# 411618_029_3_4.net
KiCad netlist of a schematic drawn in Altium Designer
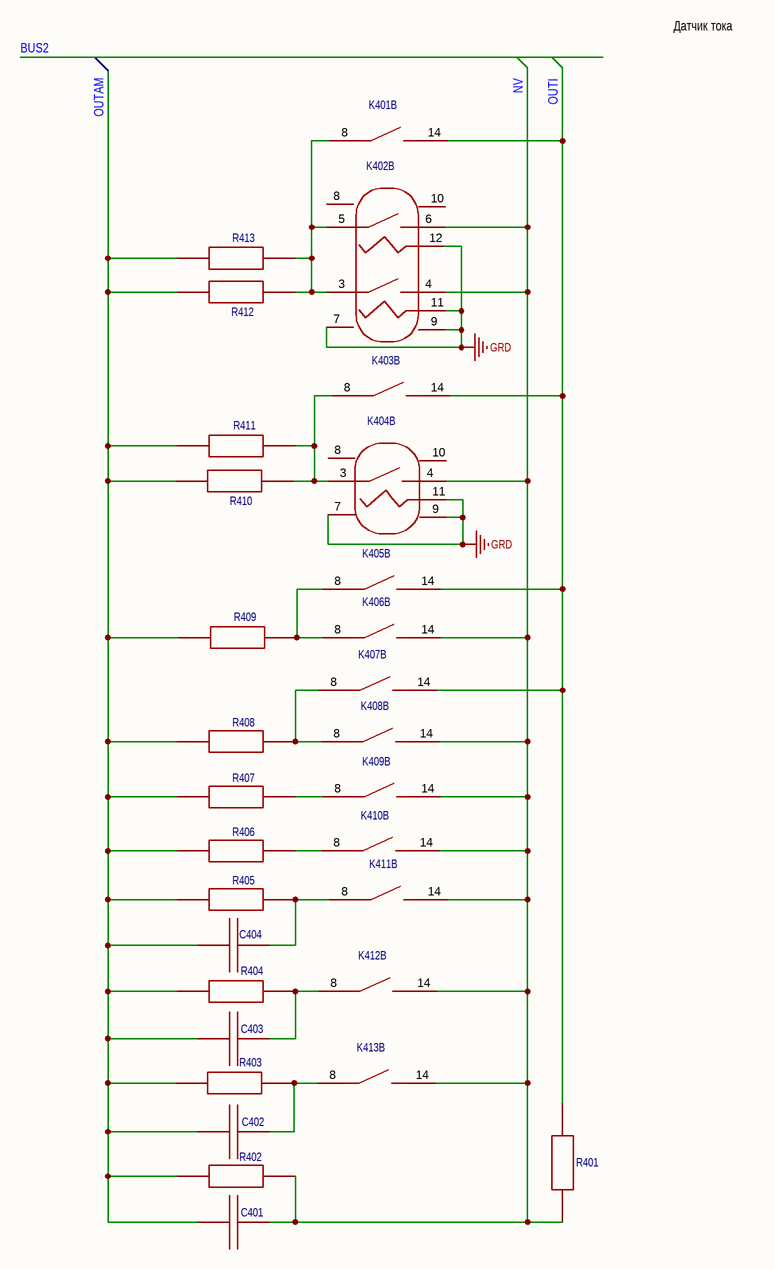
[diagram p0: УШЯИ.411618.029Э Э3 Лист 4.schdoc]

(export (version "E")
  (design (tool "Eeschema 10.0.6"))
  (components
    (comp (ref "C401")
      (value "Конденсатор К10-17Б М47 33пФ NP0 5% [DIP]")
      (fields (field (name "MANUFACTURER PART") "К10-17Б М47") (field (name "CONTRIBUTOR") "jordanjin"))
      (libsource (lib "altium-import") (part "root_2_Конденсатор К10-17Б М47 33пФ NP0 5% [DIP]_"))
    )
    (comp (ref "C402")
      (value "Конденсатор К10-17Б М47 33пФ NP0 5% [DIP]")
      (fields (field (name "MANUFACTURER PART") "К10-17Б М47") (field (name "CONTRIBUTOR") "jordanjin"))
      (libsource (lib "altium-import") (part "root_2_Конденсатор К10-17Б М47 33пФ NP0 5% [DIP]_"))
    )
    (comp (ref "C403")
      (value "Конденсатор К10-17Б М47 33пФ NP0 5% [DIP]")
      (fields (field (name "MANUFACTURER PART") "К10-17Б М47") (field (name "CONTRIBUTOR") "jordanjin"))
      (libsource (lib "altium-import") (part "root_2_Конденсатор К10-17Б М47 33пФ NP0 5% [DIP]_"))
    )
    (comp (ref "C404")
      (value "Конденсатор К10-17Б М47 33пФ NP0 5% [DIP]")
      (fields (field (name "MANUFACTURER PART") "К10-17Б М47") (field (name "CONTRIBUTOR") "jordanjin"))
      (libsource (lib "altium-import") (part "root_2_Конденсатор К10-17Б М47 33пФ NP0 5% [DIP]_"))
    )
    (comp (ref "K401")
      (value "Реле герконовое DIP05-1A72-13L  [PCB]")
      (footprint "RELAY-TH_STANDEXMEDER_DIP05-1A72-13L")
      (fields
        (field (name "MANUFACTURER") "STANDEXMEDER")
        (field (name "MANUFACTURER PART") "DIP05-1A72-13L")
        (field (name "SUBPART_NO") "1")
        (field (name "CONTRIBUTOR") "jordanjin")
      )
      (libsource (lib "altium-import") (part "root_1_Реле герконовое DIP05-1A72-13L  [PCB]_"))
    )
    (comp (ref "K402")
      (value "Реле герконовое УШЯИ.685442.092 (2 реле)")
      (fields
        (field (name "MANUFACTURER") "ОАО\"МНИПИ\"")
        (field (name "MANUFACTURER PART") "УШЯИ.685442.092")
        (field (name "PART NUMBER") "1")
        (field (name "CONTRIBUTOR") "jordanjin")
      )
      (libsource (lib "altium-import") (part "root_1_Реле герконовое УШЯИ.685442.092 (2 реле)_"))
    )
    (comp (ref "K403")
      (value "Реле герконовое DIP05-1A72-13L  [PCB]")
      (footprint "RELAY-TH_STANDEXMEDER_DIP05-1A72-13L")
      (fields
        (field (name "MANUFACTURER") "STANDEXMEDER")
        (field (name "MANUFACTURER PART") "DIP05-1A72-13L")
        (field (name "SUBPART_NO") "1")
        (field (name "CONTRIBUTOR") "jordanjin")
      )
      (libsource (lib "altium-import") (part "root_1_Реле герконовое DIP05-1A72-13L  [PCB]_"))
    )
    (comp (ref "K404")
      (value "Реле герконовое УШЯИ.685442.092 (1 реле)")
      (fields
        (field (name "MANUFACTURER") "ОАО\"МНИПИ\"")
        (field (name "MANUFACTURER PART") "УШЯИ.685442.092")
        (field (name "SUBPART_NO") "1")
        (field (name "CONTRIBUTOR") "jordanjin")
      )
      (libsource (lib "altium-import") (part "root_1_Реле герконовое УШЯИ.685442.092 (1 реле)_"))
    )
    (comp (ref "K405")
      (value "Реле герконовое DIP05-1A72-13L  [PCB]")
      (footprint "RELAY-TH_STANDEXMEDER_DIP05-1A72-13L")
      (fields
        (field (name "MANUFACTURER") "STANDEXMEDER")
        (field (name "MANUFACTURER PART") "DIP05-1A72-13L")
        (field (name "SUBPART_NO") "1")
        (field (name "CONTRIBUTOR") "jordanjin")
      )
      (libsource (lib "altium-import") (part "root_1_Реле герконовое DIP05-1A72-13L  [PCB]_"))
    )
    (comp (ref "K406")
      (value "Реле герконовое DIP05-1A72-13L  [PCB]")
      (footprint "RELAY-TH_STANDEXMEDER_DIP05-1A72-13L")
      (fields
        (field (name "MANUFACTURER") "STANDEXMEDER")
        (field (name "MANUFACTURER PART") "DIP05-1A72-13L")
        (field (name "SUBPART_NO") "1")
        (field (name "CONTRIBUTOR") "jordanjin")
      )
      (libsource (lib "altium-import") (part "root_1_Реле герконовое DIP05-1A72-13L  [PCB]_"))
    )
    (comp (ref "K407")
      (value "Реле герконовое DIP05-1A72-13L  [PCB]")
      (footprint "RELAY-TH_STANDEXMEDER_DIP05-1A72-13L")
      (fields
        (field (name "MANUFACTURER") "STANDEXMEDER")
        (field (name "MANUFACTURER PART") "DIP05-1A72-13L")
        (field (name "SUBPART_NO") "1")
        (field (name "CONTRIBUTOR") "jordanjin")
      )
      (libsource (lib "altium-import") (part "root_1_Реле герконовое DIP05-1A72-13L  [PCB]_"))
    )
    (comp (ref "K408")
      (value "Реле герконовое DIP05-1A72-13L  [PCB]")
      (footprint "RELAY-TH_STANDEXMEDER_DIP05-1A72-13L")
      (fields
        (field (name "MANUFACTURER") "STANDEXMEDER")
        (field (name "MANUFACTURER PART") "DIP05-1A72-13L")
        (field (name "SUBPART_NO") "1")
        (field (name "CONTRIBUTOR") "jordanjin")
      )
      (libsource (lib "altium-import") (part "root_1_Реле герконовое DIP05-1A72-13L  [PCB]_"))
    )
    (comp (ref "K409")
      (value "Реле герконовое DIP05-1A72-13L  [PCB]")
      (footprint "RELAY-TH_STANDEXMEDER_DIP05-1A72-13L")
      (fields
        (field (name "MANUFACTURER") "STANDEXMEDER")
        (field (name "MANUFACTURER PART") "DIP05-1A72-13L")
        (field (name "SUBPART_NO") "1")
        (field (name "CONTRIBUTOR") "jordanjin")
      )
      (libsource (lib "altium-import") (part "root_1_Реле герконовое DIP05-1A72-13L  [PCB]_"))
    )
    (comp (ref "K410")
      (value "Реле герконовое DIP05-1A72-13L  [PCB]")
      (footprint "RELAY-TH_STANDEXMEDER_DIP05-1A72-13L")
      (fields
        (field (name "MANUFACTURER") "STANDEXMEDER")
        (field (name "MANUFACTURER PART") "DIP05-1A72-13L")
        (field (name "SUBPART_NO") "1")
        (field (name "CONTRIBUTOR") "jordanjin")
      )
      (libsource (lib "altium-import") (part "root_1_Реле герконовое DIP05-1A72-13L  [PCB]_"))
    )
    (comp (ref "K411")
      (value "Реле герконовое DIP05-1A72-13L  [PCB]")
      (footprint "RELAY-TH_STANDEXMEDER_DIP05-1A72-13L")
      (fields
        (field (name "MANUFACTURER") "STANDEXMEDER")
        (field (name "MANUFACTURER PART") "DIP05-1A72-13L")
        (field (name "SUBPART_NO") "1")
        (field (name "CONTRIBUTOR") "jordanjin")
      )
      (libsource (lib "altium-import") (part "root_1_Реле герконовое DIP05-1A72-13L  [PCB]_"))
    )
    (comp (ref "K412")
      (value "Реле герконовое DIP05-1A72-13L  [PCB]")
      (footprint "RELAY-TH_STANDEXMEDER_DIP05-1A72-13L")
      (fields
        (field (name "MANUFACTURER") "STANDEXMEDER")
        (field (name "MANUFACTURER PART") "DIP05-1A72-13L")
        (field (name "SUBPART_NO") "1")
        (field (name "CONTRIBUTOR") "jordanjin")
      )
      (libsource (lib "altium-import") (part "root_1_Реле герконовое DIP05-1A72-13L  [PCB]_"))
    )
    (comp (ref "K413")
      (value "Реле герконовое DIP05-1A72-13L  [PCB]")
      (footprint "RELAY-TH_STANDEXMEDER_DIP05-1A72-13L")
      (fields
        (field (name "MANUFACTURER") "STANDEXMEDER")
        (field (name "MANUFACTURER PART") "DIP05-1A72-13L")
        (field (name "SUBPART_NO") "1")
        (field (name "CONTRIBUTOR") "jordanjin")
      )
      (libsource (lib "altium-import") (part "root_1_Реле герконовое DIP05-1A72-13L  [PCB]_"))
    )
    (comp (ref "R401")
      (value "Резистор C2-29В-0,25  24кОм ±0,5% [DIP]")
      (fields (field (name "MANUFACTURER PART") "C2-29В-0,25") (field (name "CONTRIBUTOR") "jordanjin"))
      (libsource (lib "altium-import") (part "root_1_Резистор C2-29В-0,25  24кОм ±0,5% [DIP]_"))
    )
    (comp (ref "R402")
      (value "Резистор SM204031006FE 100МОм ±1%[DIP]")
      (footprint "RES-TH_L27.4-W2.5-P22.86-D0.8")
      (fields
        (field (name "MANUFACTURER") "Ohmite")
        (field (name "MANUFACTURER PART") "SM204031006FE")
        (field (name "CONTRIBUTOR") "jordanjin")
      )
      (libsource (lib "altium-import") (part "root_2_Резистор SM204031006FE 100МОм ±1%[DIP]_"))
    )
    (comp (ref "R403")
      (value "Резистор RK1/4DCT52R1105F 11 МОм ±1% [DIP]")
      (fields
        (field (name "MANUFACTURER") "KOA Speer Electronics")
        (field (name "MANUFACTURER PART") "RK1/4DCT52R1105F")
        (field (name "CONTRIBUTOR") "jordanjin")
      )
      (libsource (lib "altium-import") (part "root_2_Резистор RK1/4DCT52R1105F 11 МОм ±1% [DIP]_"))
    )
    (comp (ref "R404")
      (value "Резистор C2-29В-0,25 1 МОм ±0,5% [DIP]")
      (fields (field (name "MANUFACTURER PART") "C2-29В-0,25") (field (name "CONTRIBUTOR") "jordanjin"))
      (libsource (lib "altium-import") (part "root_2_Резистор C2-29В-0,25 1 МОм ±0,5% [DIP]_"))
    )
    (comp (ref "R405")
      (value "Резистор C2-29В-0,25 100 кОм ±0,5% [DIP]")
      (fields (field (name "MANUFACTURER PART") "C2-29В-0,25") (field (name "CONTRIBUTOR") "jordanjin"))
      (libsource (lib "altium-import") (part "root_2_Резистор C2-29В-0,25 100 кОм ±0,5% [DIP]_"))
    )
    (comp (ref "R406")
      (value "Резистор C2-29B-1 10 кОм ±0,5% [DIP]")
      (fields (field (name "MANUFACTURER PART") "C2-29В-1") (field (name "CONTRIBUTOR") "jordanjin"))
      (libsource (lib "altium-import") (part "root_2_Резистор C2-29B-1 10 кОм ±0,5% [DIP]_"))
    )
    (comp (ref "R407")
      (value "Резистор C2-29B-1 1 кОм ±0,5% [DIP]")
      (fields (field (name "MANUFACTURER PART") "C2-29В-1") (field (name "CONTRIBUTOR") "jordanjin"))
      (libsource (lib "altium-import") (part "root_2_Резистор C2-29B-1 1 кОм ±0,5% [DIP]_"))
    )
    (comp (ref "R408")
      (value "Резистор C2-29B-1 100 Ом ±0,5% [DIP]")
      (fields (field (name "MANUFACTURER PART") "C2-29В-1") (field (name "CONTRIBUTOR") "jordanjin"))
      (libsource (lib "altium-import") (part "root_2_Резистор C2-29B-1 100 Ом ±0,5% [DIP]_"))
    )
    (comp (ref "R409")
      (value "Резистор C2-29B-2 10 Ом ±0,5% [DIP]")
      (fields (field (name "MANUFACTURER PART") "C2-29В-2") (field (name "CONTRIBUTOR") "jordanjin"))
      (libsource (lib "altium-import") (part "root_2_Резистор C2-29B-2 10 Ом ±0,5% [DIP]_"))
    )
    (comp (ref "R410")
      (value "Резистор MP930-2.00-1% [TO-220-2]")
      (footprint "TO-220-2_L10.4-W3.2-P5.08-L")
      (fields
        (field (name "MANUFACTURER") "Caddock")
        (field (name "MANUFACTURER PART") "MP930-2.00-1%")
        (field (name "CONTRIBUTOR") "jordanjin")
      )
      (libsource (lib "altium-import") (part "root_2_Резистор MP930-2.00-1% [TO-220-2]_"))
    )
    (comp (ref "R411")
      (value "Резистор MP930-2.00-1% [TO-220-2]")
      (footprint "TO-220-2_L10.4-W3.2-P5.08-L")
      (fields
        (field (name "MANUFACTURER") "Caddock")
        (field (name "MANUFACTURER PART") "MP930-2.00-1%")
        (field (name "CONTRIBUTOR") "jordanjin")
      )
      (libsource (lib "altium-import") (part "root_2_Резистор MP930-2.00-1% [TO-220-2]_"))
    )
    (comp (ref "R412")
      (value "Резистор MP930-0.20-1% [TO-220-2]")
      (footprint "TO-220-2_L10.4-W3.2-P5.08-L")
      (fields
        (field (name "MANUFACTURER") "Caddock")
        (field (name "MANUFACTURER PART") "MP930-2.00-1%")
        (field (name "CONTRIBUTOR") "jordanjin")
      )
      (libsource (lib "altium-import") (part "root_2_Резистор MP930-0.20-1% [TO-220-2]_"))
    )
    (comp (ref "R413")
      (value "Резистор MP930-0.20-1% [TO-220-2]")
      (footprint "TO-220-2_L10.4-W3.2-P5.08-L")
      (fields
        (field (name "MANUFACTURER") "Caddock")
        (field (name "MANUFACTURER PART") "MP930-2.00-1%")
        (field (name "CONTRIBUTOR") "jordanjin")
      )
      (libsource (lib "altium-import") (part "root_2_Резистор MP930-0.20-1% [TO-220-2]_"))
    )
  )
  (nets
    (net (code "2") (name "/NV") (class "Default")
      (node (ref "C401") (pin "1") (pinfunction "1_1") (pintype "passive"))
      (node (ref "K402") (pin "4") (pinfunction "4_4") (pintype "passive"))
      (node (ref "K402") (pin "6") (pinfunction "6_6") (pintype "passive"))
      (node (ref "K404") (pin "4") (pinfunction "4_4") (pintype "passive"))
      (node (ref "K406") (pin "14") (pinfunction "14_14") (pintype "passive"))
      (node (ref "K408") (pin "14") (pinfunction "14_14") (pintype "passive"))
      (node (ref "K409") (pin "14") (pinfunction "14_14") (pintype "passive"))
      (node (ref "K410") (pin "14") (pinfunction "14_14") (pintype "passive"))
      (node (ref "K411") (pin "14") (pinfunction "14_14") (pintype "passive"))
      (node (ref "K412") (pin "14") (pinfunction "14_14") (pintype "passive"))
      (node (ref "K413") (pin "14") (pinfunction "14_14") (pintype "passive"))
      (node (ref "R401") (pin "1") (pinfunction "1_1") (pintype "passive"))
      (node (ref "R402") (pin "1") (pinfunction "1_1") (pintype "passive"))
    )
    (net (code "3") (name "/OUTAM") (class "Default")
      (node (ref "C401") (pin "2") (pinfunction "2_2") (pintype "passive"))
      (node (ref "C402") (pin "2") (pinfunction "2_2") (pintype "passive"))
      (node (ref "C403") (pin "2") (pinfunction "2_2") (pintype "passive"))
      (node (ref "C404") (pin "2") (pinfunction "2_2") (pintype "passive"))
      (node (ref "R402") (pin "2") (pinfunction "2_2") (pintype "passive"))
      (node (ref "R403") (pin "2") (pinfunction "2_2") (pintype "passive"))
      (node (ref "R404") (pin "2") (pinfunction "2_2") (pintype "passive"))
      (node (ref "R405") (pin "2") (pinfunction "2_2") (pintype "passive"))
      (node (ref "R406") (pin "2") (pinfunction "2_2") (pintype "passive"))
      (node (ref "R407") (pin "2") (pinfunction "2_2") (pintype "passive"))
      (node (ref "R408") (pin "2") (pinfunction "2_2") (pintype "passive"))
      (node (ref "R409") (pin "2") (pinfunction "2_2") (pintype "passive"))
      (node (ref "R410") (pin "2") (pinfunction "2_2") (pintype "passive"))
      (node (ref "R411") (pin "2") (pinfunction "2_2") (pintype "passive"))
      (node (ref "R412") (pin "2") (pinfunction "2_2") (pintype "passive"))
      (node (ref "R413") (pin "2") (pinfunction "2_2") (pintype "passive"))
    )
    (net (code "4") (name "/OUTI") (class "Default")
      (node (ref "K401") (pin "14") (pinfunction "14_14") (pintype "passive"))
      (node (ref "K403") (pin "14") (pinfunction "14_14") (pintype "passive"))
      (node (ref "K405") (pin "14") (pinfunction "14_14") (pintype "passive"))
      (node (ref "K407") (pin "14") (pinfunction "14_14") (pintype "passive"))
      (node (ref "R401") (pin "2") (pinfunction "2_2") (pintype "passive"))
    )
    (net (code "6") (name "GRD") (class "Default")
      (node (ref "K402") (pin "11") (pinfunction "11_11") (pintype "passive"))
      (node (ref "K402") (pin "12") (pinfunction "12_12") (pintype "passive"))
      (node (ref "K402") (pin "7") (pinfunction "7_7") (pintype "passive"))
      (node (ref "K402") (pin "9") (pinfunction "9_9") (pintype "passive"))
      (node (ref "K404") (pin "11") (pinfunction "11_11") (pintype "passive"))
      (node (ref "K404") (pin "7") (pinfunction "7_7") (pintype "passive"))
      (node (ref "K404") (pin "9") (pinfunction "9_9") (pintype "passive"))
    )
    (net (code "7") (name "Net-(C402-Pad1)") (class "Default")
      (node (ref "C402") (pin "1") (pinfunction "1_1") (pintype "passive"))
      (node (ref "K413") (pin "8") (pinfunction "8_8") (pintype "passive"))
      (node (ref "R403") (pin "1") (pinfunction "1_1") (pintype "passive"))
    )
    (net (code "8") (name "Net-(C403-Pad1)") (class "Default")
      (node (ref "C403") (pin "1") (pinfunction "1_1") (pintype "passive"))
      (node (ref "K412") (pin "8") (pinfunction "8_8") (pintype "passive"))
      (node (ref "R404") (pin "1") (pinfunction "1_1") (pintype "passive"))
    )
    (net (code "9") (name "Net-(C404-Pad1)") (class "Default")
      (node (ref "C404") (pin "1") (pinfunction "1_1") (pintype "passive"))
      (node (ref "K411") (pin "8") (pinfunction "8_8") (pintype "passive"))
      (node (ref "R405") (pin "1") (pinfunction "1_1") (pintype "passive"))
    )
    (net (code "10") (name "Net-(K401-Pad8)") (class "Default")
      (node (ref "K401") (pin "8") (pinfunction "8_8") (pintype "passive"))
      (node (ref "K402") (pin "3") (pinfunction "3_3") (pintype "passive"))
      (node (ref "K402") (pin "5") (pinfunction "5_5") (pintype "passive"))
      (node (ref "R412") (pin "1") (pinfunction "1_1") (pintype "passive"))
      (node (ref "R413") (pin "1") (pinfunction "1_1") (pintype "passive"))
    )
    (net (code "11") (name "Net-(K403-Pad8)") (class "Default")
      (node (ref "K403") (pin "8") (pinfunction "8_8") (pintype "passive"))
      (node (ref "K404") (pin "3") (pinfunction "3_3") (pintype "passive"))
      (node (ref "R410") (pin "1") (pinfunction "1_1") (pintype "passive"))
      (node (ref "R411") (pin "1") (pinfunction "1_1") (pintype "passive"))
    )
    (net (code "12") (name "Net-(K405-Pad8)") (class "Default")
      (node (ref "K405") (pin "8") (pinfunction "8_8") (pintype "passive"))
      (node (ref "K406") (pin "8") (pinfunction "8_8") (pintype "passive"))
      (node (ref "R409") (pin "1") (pinfunction "1_1") (pintype "passive"))
    )
    (net (code "13") (name "Net-(K407-Pad8)") (class "Default")
      (node (ref "K407") (pin "8") (pinfunction "8_8") (pintype "passive"))
      (node (ref "K408") (pin "8") (pinfunction "8_8") (pintype "passive"))
      (node (ref "R408") (pin "1") (pinfunction "1_1") (pintype "passive"))
    )
    (net (code "14") (name "Net-(K409-Pad8)") (class "Default")
      (node (ref "K409") (pin "8") (pinfunction "8_8") (pintype "passive"))
      (node (ref "R407") (pin "1") (pinfunction "1_1") (pintype "passive"))
    )
    (net (code "15") (name "Net-(K410-Pad8)") (class "Default")
      (node (ref "K410") (pin "8") (pinfunction "8_8") (pintype "passive"))
      (node (ref "R406") (pin "1") (pinfunction "1_1") (pintype "passive"))
    )
    (net (code "16") (name "unconnected-(K402-Pad8)") (class "Default")
      (node (ref "K402") (pin "8") (pinfunction "8_8") (pintype "passive"))
    )
    (net (code "17") (name "unconnected-(K402-Pad10)") (class "Default")
      (node (ref "K402") (pin "10") (pinfunction "10_10") (pintype "passive"))
    )
    (net (code "18") (name "unconnected-(K404-Pad8)") (class "Default")
      (node (ref "K404") (pin "8") (pinfunction "8_8") (pintype "passive"))
    )
    (net (code "19") (name "unconnected-(K404-Pad10)") (class "Default")
      (node (ref "K404") (pin "10") (pinfunction "10_10") (pintype "passive"))
    )
  )
)
